# Proiect_TSC.net
KiCad netlist of a schematic drawn in EAGLE
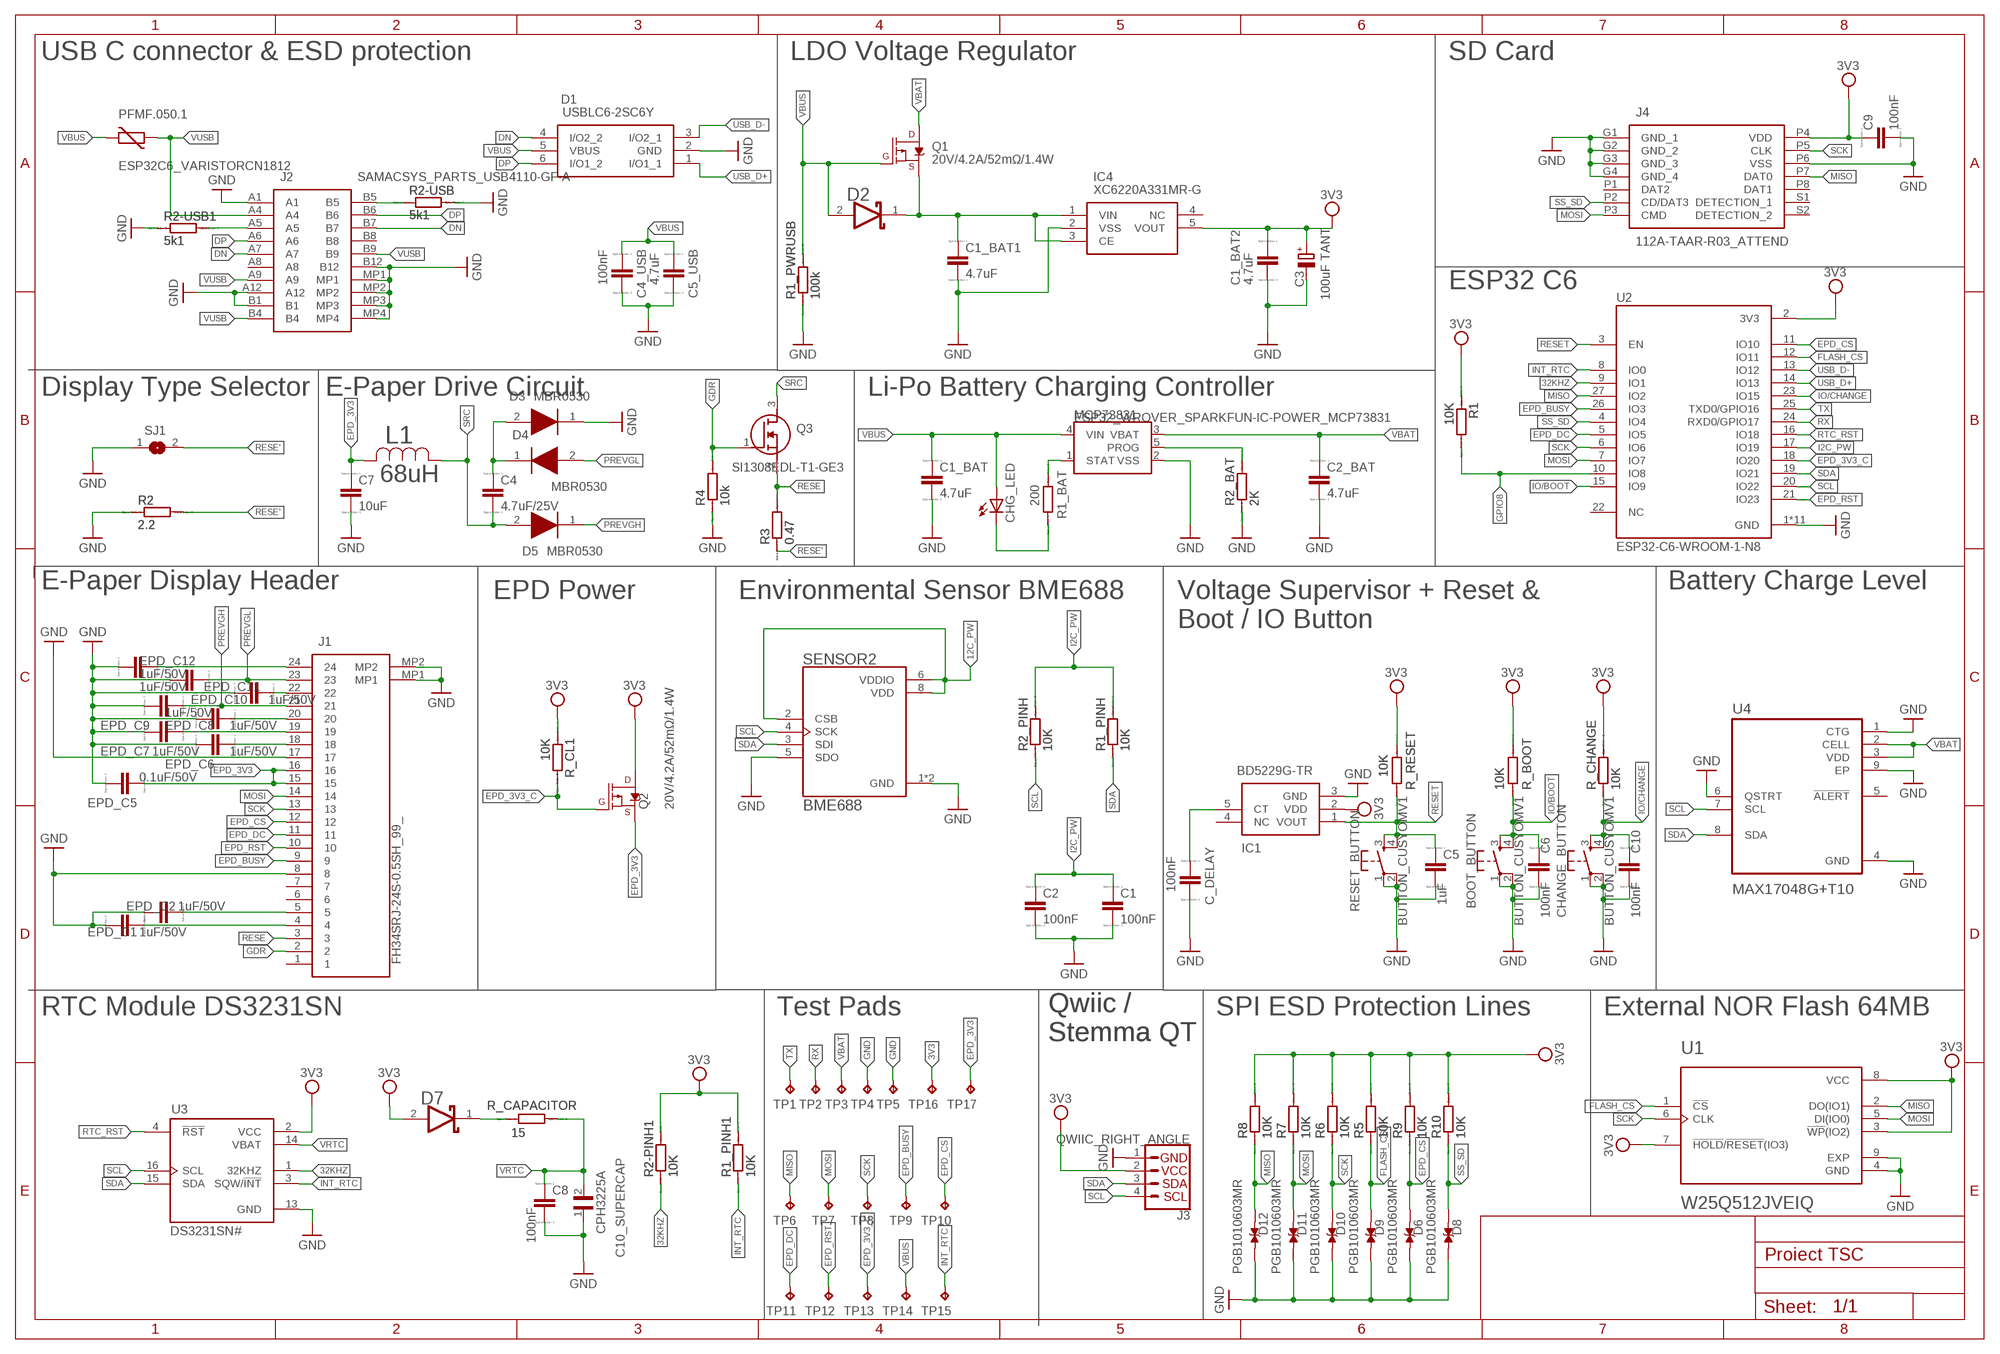
[diagram p0: schematic, sheet 1]

(export (version "E")
  (design (tool "Eeschema 10.0.6"))
  (components
    (comp (ref "BOOT_BUTTON")
      (value "BUTTON_CUSYOMV1")
      (footprint "eagle-import:MYBUTTON")
      (libsource (lib "eagle-import") (part "BUTTON_CUSYOMV1"))
    )
    (comp (ref "C1")
      (value "100nF")
      (footprint "eagle-import:EAGLE-LTSPICE_C0402")
      (libsource (lib "eagle-import") (part "EAGLE-LTSPICE_CC0402"))
    )
    (comp (ref "C1_BAT")
      (value "4.7uF")
      (footprint "eagle-import:EAGLE-LTSPICE_C0402")
      (libsource (lib "eagle-import") (part "EAGLE-LTSPICE_CC0402"))
    )
    (comp (ref "C1_BAT1")
      (value "4.7uF")
      (footprint "eagle-import:EAGLE-LTSPICE_C0402")
      (libsource (lib "eagle-import") (part "EAGLE-LTSPICE_CC0402"))
    )
    (comp (ref "C1_BAT2")
      (value "4.7uF")
      (footprint "eagle-import:EAGLE-LTSPICE_C0402")
      (libsource (lib "eagle-import") (part "EAGLE-LTSPICE_CC0402"))
    )
    (comp (ref "C2")
      (value "100nF")
      (footprint "eagle-import:EAGLE-LTSPICE_C0402")
      (libsource (lib "eagle-import") (part "EAGLE-LTSPICE_CC0402"))
    )
    (comp (ref "C2_BAT")
      (value "4.7uF")
      (footprint "eagle-import:EAGLE-LTSPICE_C0402")
      (libsource (lib "eagle-import") (part "EAGLE-LTSPICE_CC0402"))
    )
    (comp (ref "C3")
      (value "100uF TANT")
      (footprint "eagle-import:RCL_CT3528")
      (libsource (lib "eagle-import") (part "RCL_CPOL-EUCT3528"))
    )
    (comp (ref "C4")
      (value "4.7uF/25V")
      (footprint "eagle-import:EAGLE-LTSPICE_C0402")
      (libsource (lib "eagle-import") (part "EAGLE-LTSPICE_CC0402"))
    )
    (comp (ref "C4_USB")
      (value "100nF")
      (footprint "eagle-import:EAGLE-LTSPICE_C0402")
      (libsource (lib "eagle-import") (part "EAGLE-LTSPICE_CC0402"))
    )
    (comp (ref "C5")
      (value "1uF")
      (footprint "eagle-import:EAGLE-LTSPICE_C0402")
      (libsource (lib "eagle-import") (part "EAGLE-LTSPICE_CC0402"))
    )
    (comp (ref "C5_USB")
      (value "4.7uF")
      (footprint "eagle-import:EAGLE-LTSPICE_C0402")
      (libsource (lib "eagle-import") (part "EAGLE-LTSPICE_CC0402"))
    )
    (comp (ref "C6")
      (value "100nF")
      (footprint "eagle-import:EAGLE-LTSPICE_C0402")
      (libsource (lib "eagle-import") (part "EAGLE-LTSPICE_CC0402"))
    )
    (comp (ref "C7")
      (value "10uF")
      (footprint "eagle-import:EAGLE-LTSPICE_C0402")
      (libsource (lib "eagle-import") (part "EAGLE-LTSPICE_CC0402"))
    )
    (comp (ref "C8")
      (value "100nF")
      (footprint "eagle-import:EAGLE-LTSPICE_C0402")
      (libsource (lib "eagle-import") (part "EAGLE-LTSPICE_CC0402"))
    )
    (comp (ref "C9")
      (value "100nF")
      (footprint "eagle-import:EAGLE-LTSPICE_C0402")
      (libsource (lib "eagle-import") (part "EAGLE-LTSPICE_CC0402"))
    )
    (comp (ref "C10")
      (value "100nF")
      (footprint "eagle-import:EAGLE-LTSPICE_C0402")
      (libsource (lib "eagle-import") (part "EAGLE-LTSPICE_CC0402"))
    )
    (comp (ref "C10_SUPERCAP")
      (value "CPH3225A")
      (footprint "eagle-import:CAPCP3225X100N")
      (fields (field (name "MF") "Seiko Instruments"))
      (libsource (lib "eagle-import") (part "CPH3225A"))
    )
    (comp (ref "CHANGE_BUTTON")
      (value "BUTTON_CUSYOMV1")
      (footprint "eagle-import:MYBUTTON")
      (libsource (lib "eagle-import") (part "BUTTON_CUSYOMV1"))
    )
    (comp (ref "CHG_LED")
      (value "ADAFRUIT_LEDCHIP-LED0603")
      (footprint "eagle-import:ADAFRUIT_CHIP-LED0603")
      (libsource (lib "eagle-import") (part "ADAFRUIT_LEDCHIP-LED0603"))
    )
    (comp (ref "C_DELAY")
      (value "100nF")
      (footprint "eagle-import:EAGLE-LTSPICE_C0402")
      (libsource (lib "eagle-import") (part "EAGLE-LTSPICE_CC0402"))
    )
    (comp (ref "D1")
      (value "USBLC6-2SC6Y")
      (footprint "eagle-import:SOT95P280X145-6N")
      (fields (field (name "MF") "STMicroelectronics"))
      (libsource (lib "eagle-import") (part "USBLC6-2SC6Y"))
    )
    (comp (ref "D2")
      (value "SD0805S020S1R0")
      (footprint "eagle-import:ESP32_WROVER_AVX---SD0805S020S1R0_AVX_SD0805S020S1R0_0")
      (fields
        (field (name "DIGIKEY_PART_NUMBER") "478-7800-1-ND")
        (field (name "MF") "AVX")
        (field (name "MOUSER_PART_NUMBER") "581-SD0805S020S1R0")
      )
      (libsource (lib "eagle-import") (part "ESP32_WROVER_AVX---SD0805S020S1R0_AVX_SD0805S020S1R0_0_0AVX_SD0805S020S1R0_0_0"))
    )
    (comp (ref "D3")
      (value "MBR0530")
      (footprint "eagle-import:SOD3716X135N")
      (fields (field (name "MF") "ON Semiconductor"))
      (libsource (lib "eagle-import") (part "MBR0530"))
    )
    (comp (ref "D4")
      (value "MBR0530")
      (footprint "eagle-import:SOD3716X135N")
      (fields (field (name "MF") "ON Semiconductor"))
      (libsource (lib "eagle-import") (part "MBR0530"))
    )
    (comp (ref "D5")
      (value "MBR0530")
      (footprint "eagle-import:SOD3716X135N")
      (fields (field (name "MF") "ON Semiconductor"))
      (libsource (lib "eagle-import") (part "MBR0530"))
    )
    (comp (ref "D6")
      (value "PGB1010603MR")
      (footprint "eagle-import:DIOC1608X36N")
      (fields (field (name "MF") "Littelfuse Inc."))
      (libsource (lib "eagle-import") (part "PGB1010603MR"))
    )
    (comp (ref "D7")
      (value "ESP32_WROVER_AVX---SD0805S020S1R0_AVX_SD0805S020S1R0_0_0AVX_SD0805S020S1R0_0_0")
      (footprint "eagle-import:ESP32_WROVER_AVX---SD0805S020S1R0_AVX_SD0805S020S1R0_0")
      (fields
        (field (name "DIGIKEY_PART_NUMBER") "478-7800-1-ND")
        (field (name "MF") "AVX")
        (field (name "MOUSER_PART_NUMBER") "581-SD0805S020S1R0")
      )
      (libsource (lib "eagle-import") (part "ESP32_WROVER_AVX---SD0805S020S1R0_AVX_SD0805S020S1R0_0_0AVX_SD0805S020S1R0_0_0"))
    )
    (comp (ref "D8")
      (value "PGB1010603MR")
      (footprint "eagle-import:DIOC1608X36N")
      (fields (field (name "MF") "Littelfuse Inc."))
      (libsource (lib "eagle-import") (part "PGB1010603MR"))
    )
    (comp (ref "D9")
      (value "PGB1010603MR")
      (footprint "eagle-import:DIOC1608X36N")
      (fields (field (name "MF") "Littelfuse Inc."))
      (libsource (lib "eagle-import") (part "PGB1010603MR"))
    )
    (comp (ref "D10")
      (value "PGB1010603MR")
      (footprint "eagle-import:DIOC1608X36N")
      (fields (field (name "MF") "Littelfuse Inc."))
      (libsource (lib "eagle-import") (part "PGB1010603MR"))
    )
    (comp (ref "D11")
      (value "PGB1010603MR")
      (footprint "eagle-import:DIOC1608X36N")
      (fields (field (name "MF") "Littelfuse Inc."))
      (libsource (lib "eagle-import") (part "PGB1010603MR"))
    )
    (comp (ref "D12")
      (value "PGB1010603MR")
      (footprint "eagle-import:DIOC1608X36N")
      (fields (field (name "MF") "Littelfuse Inc."))
      (libsource (lib "eagle-import") (part "PGB1010603MR"))
    )
    (comp (ref "EPD_C1")
      (value "1uF/50V")
      (footprint "eagle-import:EAGLE-LTSPICE_C0402")
      (libsource (lib "eagle-import") (part "EAGLE-LTSPICE_CC0402"))
    )
    (comp (ref "EPD_C2")
      (value "1uF/50V")
      (footprint "eagle-import:EAGLE-LTSPICE_C0402")
      (libsource (lib "eagle-import") (part "EAGLE-LTSPICE_CC0402"))
    )
    (comp (ref "EPD_C5")
      (value "0.1uF/50V")
      (footprint "eagle-import:EAGLE-LTSPICE_C0402")
      (libsource (lib "eagle-import") (part "EAGLE-LTSPICE_CC0402"))
    )
    (comp (ref "EPD_C6")
      (value "1uF/50V")
      (footprint "eagle-import:EAGLE-LTSPICE_C0402")
      (libsource (lib "eagle-import") (part "EAGLE-LTSPICE_CC0402"))
    )
    (comp (ref "EPD_C7")
      (value "1uF/50V")
      (footprint "eagle-import:EAGLE-LTSPICE_C0402")
      (libsource (lib "eagle-import") (part "EAGLE-LTSPICE_CC0402"))
    )
    (comp (ref "EPD_C8")
      (value "1uF/50V")
      (footprint "eagle-import:EAGLE-LTSPICE_C0402")
      (libsource (lib "eagle-import") (part "EAGLE-LTSPICE_CC0402"))
    )
    (comp (ref "EPD_C9")
      (value "1uF/50V")
      (footprint "eagle-import:EAGLE-LTSPICE_C0402")
      (libsource (lib "eagle-import") (part "EAGLE-LTSPICE_CC0402"))
    )
    (comp (ref "EPD_C10")
      (value "1uF/50V")
      (footprint "eagle-import:EAGLE-LTSPICE_C0402")
      (libsource (lib "eagle-import") (part "EAGLE-LTSPICE_CC0402"))
    )
    (comp (ref "EPD_C11")
      (value "1uF/50V")
      (footprint "eagle-import:EAGLE-LTSPICE_C0402")
      (libsource (lib "eagle-import") (part "EAGLE-LTSPICE_CC0402"))
    )
    (comp (ref "EPD_C12")
      (value "1uF/50V")
      (footprint "eagle-import:EAGLE-LTSPICE_C0402")
      (libsource (lib "eagle-import") (part "EAGLE-LTSPICE_CC0402"))
    )
    (comp (ref "IC1")
      (value "BD5229G-TR")
      (footprint "eagle-import:SOT95P280X120-5N")
      (fields (field (name "MOUSER_PART_NUMBER") "755-BD5229G-TR"))
      (libsource (lib "eagle-import") (part "BD5229G-TR"))
    )
    (comp (ref "IC4")
      (value "XC6220A331MR-G")
      (footprint "eagle-import:SOT95P280X120-5N")
      (fields (field (name "MOUSER_PART_NUMBER") "865-XC6220A331MR-G"))
      (libsource (lib "eagle-import") (part "XC6220A331MR-G"))
    )
    (comp (ref "J1")
      (value "FH34SRJ-24S-0.5SH_99_")
      (footprint "eagle-import:FH34SRJ24S05SH99")
      (fields
        (field (name "MANUFACTURER_PART_NUMBER") "FH34SRJ-24S-0.5SH(99)")
        (field (name "MOUSER_PART_NUMBER") "798-FH34SRJ24S05SH99")
      )
      (libsource (lib "eagle-import") (part "FH34SRJ-24S-0.5SH_99_"))
    )
    (comp (ref "J2")
      (value "SAMACSYS_PARTS_USB4110-GF-A")
      (footprint "eagle-import:SAMACSYS_PARTS_USB4110GFA")
      (fields
        (field (name "MANUFACTURER_PART_NUMBER") "USB4110-GF-A")
        (field (name "MOUSER_PART_NUMBER") "640-USB4110-GF-A")
      )
      (libsource (lib "eagle-import") (part "SAMACSYS_PARTS_USB4110-GF-A"))
    )
    (comp (ref "J3")
      (value "QWIIC_RIGHT_ANGLE")
      (footprint "eagle-import:JST04_1MM_RA")
      (libsource (lib "eagle-import") (part "QWIIC_CONNECTORJS-1MM"))
    )
    (comp (ref "J4")
      (value "112A-TAAR-R03_ATTEND")
      (footprint "eagle-import:112ATAARR03ATTEND")
      (fields (field (name "MANUFACTURER_PART_NUMBER") "112A-TAAR-R03 ATTEND"))
      (libsource (lib "eagle-import") (part "112A-TAAR-R03_ATTEND"))
    )
    (comp (ref "L1")
      (value "68uH")
      (footprint "eagle-import:IND_4828-WE-TPC_WRE")
      (fields
        (field (name "MANUFACTURER_PART_NUMBER") "744043680")
        (field (name "COPYRIGHT") "Copyright (C) 2024 Ultra Librarian. All rights reserved.")
      )
      (libsource (lib "eagle-import") (part "744043680IND_4828-WE-TPC_WRE"))
    )
    (comp (ref "MCP73831")
      (value "ESP32_WROVER_SPARKFUN-IC-POWER_MCP73831")
      (footprint "eagle-import:ESP32_WROVER_SPARKFUN-IC-POWER_SOT23-5")
      (libsource (lib "eagle-import") (part "ESP32_WROVER_SPARKFUN-IC-POWER_MCP73831"))
    )
    (comp (ref "PFMF.050.1")
      (value "ESP32C6_VARISTORCN1812")
      (footprint "eagle-import:ESP32C6_VARISTOR_CT_CN1812")
      (libsource (lib "eagle-import") (part "ESP32C6_VARISTORCN1812"))
    )
    (comp (ref "Q1")
      (value "20V/4.2A/52mΩ/1.4W")
      (footprint "eagle-import:ESP32_WROVER_SPARKFUN-DISCRETESEMI_SOT23-3")
      (libsource (lib "eagle-import") (part "ESP32_WROVER_SPARKFUN-DISCRETESEMI_MOSFET_PCH-DMG2305UX-7"))
    )
    (comp (ref "Q2")
      (value "20V/4.2A/52mΩ/1.4W")
      (footprint "eagle-import:ESP32_WROVER_SPARKFUN-DISCRETESEMI_SOT23-3")
      (libsource (lib "eagle-import") (part "ESP32_WROVER_SPARKFUN-DISCRETESEMI_MOSFET_PCH-DMG2305UX-7"))
    )
    (comp (ref "Q3")
      (value "SI1308EDL-T1-GE3")
      (footprint "eagle-import:SOT65P210X110-3N")
      (fields (field (name "MF") "Vishay Siliconix"))
      (libsource (lib "eagle-import") (part "SI1308EDL-T1-GE3"))
    )
    (comp (ref "R1")
      (value "10K")
      (footprint "eagle-import:ESP32_WROVER_EAGLE-LTSPICE_R0402")
      (libsource (lib "eagle-import") (part "ESP32_WROVER_EAGLE-LTSPICE_RR0402"))
    )
    (comp (ref "R1_BAT")
      (value "200")
      (footprint "eagle-import:ESP32_WROVER_EAGLE-LTSPICE_R0402")
      (libsource (lib "eagle-import") (part "ESP32_WROVER_EAGLE-LTSPICE_RR0402"))
    )
    (comp (ref "R1_PINH")
      (value "10K")
      (footprint "eagle-import:ESP32_WROVER_EAGLE-LTSPICE_R0402")
      (libsource (lib "eagle-import") (part "ESP32_WROVER_EAGLE-LTSPICE_RR0402"))
    )
    (comp (ref "R1_PINH1")
      (value "10K")
      (footprint "eagle-import:ESP32_WROVER_EAGLE-LTSPICE_R0402")
      (libsource (lib "eagle-import") (part "ESP32_WROVER_EAGLE-LTSPICE_RR0402"))
    )
    (comp (ref "R1_PWRUSB")
      (value "100k")
      (footprint "eagle-import:ESP32_WROVER_EAGLE-LTSPICE_R0402")
      (libsource (lib "eagle-import") (part "ESP32_WROVER_EAGLE-LTSPICE_RR0402"))
    )
    (comp (ref "R2")
      (value "2.2")
      (footprint "eagle-import:ESP32_WROVER_EAGLE-LTSPICE_R0402")
      (libsource (lib "eagle-import") (part "ESP32_WROVER_EAGLE-LTSPICE_RR0402"))
    )
    (comp (ref "R2-PINH1")
      (value "10K")
      (footprint "eagle-import:ESP32_WROVER_EAGLE-LTSPICE_R0402")
      (libsource (lib "eagle-import") (part "ESP32_WROVER_EAGLE-LTSPICE_RR0402"))
    )
    (comp (ref "R2-USB")
      (value "5k1")
      (footprint "eagle-import:ESP32_WROVER_EAGLE-LTSPICE_R0402")
      (libsource (lib "eagle-import") (part "ESP32_WROVER_EAGLE-LTSPICE_RR0402"))
    )
    (comp (ref "R2-USB1")
      (value "5k1")
      (footprint "eagle-import:ESP32_WROVER_EAGLE-LTSPICE_R0402")
      (libsource (lib "eagle-import") (part "ESP32_WROVER_EAGLE-LTSPICE_RR0402"))
    )
    (comp (ref "R2_BAT")
      (value "2K")
      (footprint "eagle-import:ESP32_WROVER_EAGLE-LTSPICE_R0402")
      (libsource (lib "eagle-import") (part "ESP32_WROVER_EAGLE-LTSPICE_RR0402"))
    )
    (comp (ref "R2_PINH")
      (value "10K")
      (footprint "eagle-import:ESP32_WROVER_EAGLE-LTSPICE_R0402")
      (libsource (lib "eagle-import") (part "ESP32_WROVER_EAGLE-LTSPICE_RR0402"))
    )
    (comp (ref "R3")
      (value "0.47")
      (footprint "eagle-import:ESP32_WROVER_EAGLE-LTSPICE_R0402")
      (libsource (lib "eagle-import") (part "ESP32_WROVER_EAGLE-LTSPICE_RR0402"))
    )
    (comp (ref "R4")
      (value "10k")
      (footprint "eagle-import:ESP32_WROVER_EAGLE-LTSPICE_R0402")
      (libsource (lib "eagle-import") (part "ESP32_WROVER_EAGLE-LTSPICE_RR0402"))
    )
    (comp (ref "R5")
      (value "10K")
      (footprint "eagle-import:ESP32_WROVER_EAGLE-LTSPICE_R0402")
      (libsource (lib "eagle-import") (part "ESP32_WROVER_EAGLE-LTSPICE_RR0402"))
    )
    (comp (ref "R6")
      (value "10K")
      (footprint "eagle-import:ESP32_WROVER_EAGLE-LTSPICE_R0402")
      (libsource (lib "eagle-import") (part "ESP32_WROVER_EAGLE-LTSPICE_RR0402"))
    )
    (comp (ref "R7")
      (value "10K")
      (footprint "eagle-import:ESP32_WROVER_EAGLE-LTSPICE_R0402")
      (libsource (lib "eagle-import") (part "ESP32_WROVER_EAGLE-LTSPICE_RR0402"))
    )
    (comp (ref "R8")
      (value "10K")
      (footprint "eagle-import:ESP32_WROVER_EAGLE-LTSPICE_R0402")
      (libsource (lib "eagle-import") (part "ESP32_WROVER_EAGLE-LTSPICE_RR0402"))
    )
    (comp (ref "R9")
      (value "10K")
      (footprint "eagle-import:ESP32_WROVER_EAGLE-LTSPICE_R0402")
      (libsource (lib "eagle-import") (part "ESP32_WROVER_EAGLE-LTSPICE_RR0402"))
    )
    (comp (ref "R10")
      (value "10K")
      (footprint "eagle-import:ESP32_WROVER_EAGLE-LTSPICE_R0402")
      (libsource (lib "eagle-import") (part "ESP32_WROVER_EAGLE-LTSPICE_RR0402"))
    )
    (comp (ref "RESET_BUTTON")
      (value "BUTTON_CUSYOMV1")
      (footprint "eagle-import:MYBUTTON")
      (libsource (lib "eagle-import") (part "BUTTON_CUSYOMV1"))
    )
    (comp (ref "R_BOOT")
      (value "10K")
      (footprint "eagle-import:ESP32_WROVER_EAGLE-LTSPICE_R0402")
      (libsource (lib "eagle-import") (part "ESP32_WROVER_EAGLE-LTSPICE_RR0402"))
    )
    (comp (ref "R_CAPACITOR")
      (value "15")
      (footprint "eagle-import:ESP32_WROVER_EAGLE-LTSPICE_R0402")
      (libsource (lib "eagle-import") (part "ESP32_WROVER_EAGLE-LTSPICE_RR0402"))
    )
    (comp (ref "R_CHANGE")
      (value "10K")
      (footprint "eagle-import:ESP32_WROVER_EAGLE-LTSPICE_R0402")
      (libsource (lib "eagle-import") (part "ESP32_WROVER_EAGLE-LTSPICE_RR0402"))
    )
    (comp (ref "R_CL1")
      (value "10K")
      (footprint "eagle-import:ESP32_WROVER_EAGLE-LTSPICE_R0402")
      (libsource (lib "eagle-import") (part "ESP32_WROVER_EAGLE-LTSPICE_RR0402"))
    )
    (comp (ref "R_RESET")
      (value "10K")
      (footprint "eagle-import:ESP32_WROVER_EAGLE-LTSPICE_R0402")
      (libsource (lib "eagle-import") (part "ESP32_WROVER_EAGLE-LTSPICE_RR0402"))
    )
    (comp (ref "SENSOR2")
      (value "BME688")
      (footprint "eagle-import:ESP32_WROVER_BME680_PSON80P300X300X100-8N")
      (fields (field (name "MF") "Bosch Sensortec") (field (name "MP") "BME680"))
      (libsource (lib "eagle-import") (part "ESP32_WROVER_BME680_BME680"))
    )
    (comp (ref "SJ1") (value "SJ") (footprint "eagle-import:SJ") (libsource (lib "eagle-import") (part "SJ")))
    (comp (ref "TP1")
      (value "TPTP20R")
      (footprint "eagle-import:TP20R")
      (libsource (lib "eagle-import") (part "TPTP20R"))
    )
    (comp (ref "TP2")
      (value "TPTP20R")
      (footprint "eagle-import:TP20R")
      (libsource (lib "eagle-import") (part "TPTP20R"))
    )
    (comp (ref "TP3")
      (value "TPTP20R")
      (footprint "eagle-import:TP20R")
      (libsource (lib "eagle-import") (part "TPTP20R"))
    )
    (comp (ref "TP4")
      (value "TPTP20R")
      (footprint "eagle-import:TP20R")
      (libsource (lib "eagle-import") (part "TPTP20R"))
    )
    (comp (ref "TP5")
      (value "TPTP20R")
      (footprint "eagle-import:TP20R")
      (libsource (lib "eagle-import") (part "TPTP20R"))
    )
    (comp (ref "TP6")
      (value "TPTP20R")
      (footprint "eagle-import:TP20R")
      (libsource (lib "eagle-import") (part "TPTP20R"))
    )
    (comp (ref "TP7")
      (value "TPTP20R")
      (footprint "eagle-import:TP20R")
      (libsource (lib "eagle-import") (part "TPTP20R"))
    )
    (comp (ref "TP8")
      (value "TPTP20R")
      (footprint "eagle-import:TP20R")
      (libsource (lib "eagle-import") (part "TPTP20R"))
    )
    (comp (ref "TP9")
      (value "TPTP20R")
      (footprint "eagle-import:TP20R")
      (libsource (lib "eagle-import") (part "TPTP20R"))
    )
    (comp (ref "TP10")
      (value "TPTP20R")
      (footprint "eagle-import:TP20R")
      (libsource (lib "eagle-import") (part "TPTP20R"))
    )
    (comp (ref "TP11")
      (value "TPTP20R")
      (footprint "eagle-import:TP20R")
      (libsource (lib "eagle-import") (part "TPTP20R"))
    )
    (comp (ref "TP12")
      (value "TPTP20R")
      (footprint "eagle-import:TP20R")
      (libsource (lib "eagle-import") (part "TPTP20R"))
    )
    (comp (ref "TP13")
      (value "TPTP20R")
      (footprint "eagle-import:TP20R")
      (libsource (lib "eagle-import") (part "TPTP20R"))
    )
    (comp (ref "TP14")
      (value "TPTP20R")
      (footprint "eagle-import:TP20R")
      (libsource (lib "eagle-import") (part "TPTP20R"))
    )
    (comp (ref "TP15")
      (value "TPTP20R")
      (footprint "eagle-import:TP20R")
      (libsource (lib "eagle-import") (part "TPTP20R"))
    )
    (comp (ref "TP16")
      (value "TPTP20R")
      (footprint "eagle-import:TP20R")
      (libsource (lib "eagle-import") (part "TPTP20R"))
    )
    (comp (ref "TP17")
      (value "TPTP20R")
      (footprint "eagle-import:TP20R")
      (libsource (lib "eagle-import") (part "TPTP20R"))
    )
    (comp (ref "U1")
      (value "W25Q512JVEIQ")
      (footprint "eagle-import:SON127P600X800X80-9N")
      (fields (field (name "MF") "Winbond Electronics"))
      (libsource (lib "eagle-import") (part "W25Q512JVEIQ"))
    )
    (comp (ref "U2")
      (value "ESP32-C6-WROOM-1-N8")
      (footprint "eagle-import:XCVR_ESP32-C6-WROOM-1-N8")
      (fields (field (name "MF") "Espressif Systems"))
      (libsource (lib "eagle-import") (part "ESP32-C6-WROOM-1-N8"))
    )
    (comp (ref "U3")
      (value "DS3231SN#")
      (footprint "eagle-import:SOIC127P1032X265-16N")
      (fields (field (name "MF") "Analog Devices"))
      (libsource (lib "eagle-import") (part "DS3231SN#"))
    )
    (comp (ref "U4")
      (value "MAX17048G+T10")
      (footprint "eagle-import:SON50P200X200X80-9N")
      (fields (field (name "MF") "Analog Devices"))
      (libsource (lib "eagle-import") (part "MAX17048G+T10"))
    )
  )
  (nets
    (net (code "1") (name "3V3") (class "Default")
      (node (ref "C1_BAT2") (pin "1") (pinfunction "1_1") (pintype "passive"))
      (node (ref "C3") (pin "+") (pinfunction "+_+") (pintype "passive"))
      (node (ref "C9") (pin "1") (pinfunction "1_1") (pintype "passive"))
      (node (ref "D7") (pin "2") (pinfunction "ANODE_2") (pintype "bidirectional"))
      (node (ref "IC1") (pin "2") (pinfunction "VDD_2") (pintype "bidirectional"))
      (node (ref "IC4") (pin "5") (pinfunction "VOUT_5") (pintype "bidirectional"))
      (node (ref "J3") (pin "2") (pinfunction "2_2") (pintype "power_in"))
      (node (ref "J4") (pin "P4") (pinfunction "VDD_P4") (pintype "bidirectional"))
      (node (ref "Q2") (pin "3") (pinfunction "D_3") (pintype "bidirectional"))
      (node (ref "R1") (pin "1") (pinfunction "1_1") (pintype "passive"))
      (node (ref "R10") (pin "2") (pinfunction "2_2") (pintype "passive"))
      (node (ref "R1_PINH1") (pin "2") (pinfunction "2_2") (pintype "passive"))
      (node (ref "R2-PINH1") (pin "2") (pinfunction "2_2") (pintype "passive"))
      (node (ref "R5") (pin "2") (pinfunction "2_2") (pintype "passive"))
      (node (ref "R6") (pin "2") (pinfunction "2_2") (pintype "passive"))
      (node (ref "R7") (pin "2") (pinfunction "2_2") (pintype "passive"))
      (node (ref "R8") (pin "2") (pinfunction "2_2") (pintype "passive"))
      (node (ref "R9") (pin "2") (pinfunction "2_2") (pintype "passive"))
      (node (ref "R_BOOT") (pin "2") (pinfunction "2_2") (pintype "passive"))
      (node (ref "R_CHANGE") (pin "2") (pinfunction "2_2") (pintype "passive"))
      (node (ref "R_CL1") (pin "1") (pinfunction "1_1") (pintype "passive"))
      (node (ref "R_RESET") (pin "2") (pinfunction "2_2") (pintype "passive"))
      (node (ref "TP16") (pin "TP") (pinfunction "TP_TP") (pintype "input"))
      (node (ref "U1") (pin "3") (pinfunction "~{WP}(IO2)_3") (pintype "bidirectional"))
      (node (ref "U1") (pin "7") (pinfunction "~{HOLD}/~{RESET}(IO3)_7") (pintype "bidirectional"))
      (node (ref "U1") (pin "8") (pinfunction "VCC_8") (pintype "power_in"))
      (node (ref "U2") (pin "2") (pinfunction "3V3_2") (pintype "power_in"))
      (node (ref "U3") (pin "2") (pinfunction "VCC_2") (pintype "power_in"))
    )
    (net (code "2") (name "12C_PW") (class "Default")
      (node (ref "SENSOR2") (pin "2") (pinfunction "CSB_2") (pintype "input"))
      (node (ref "SENSOR2") (pin "6") (pinfunction "VDDIO_6") (pintype "power_in"))
      (node (ref "SENSOR2") (pin "8") (pinfunction "VDD_8") (pintype "power_in"))
    )
    (net (code "3") (name "32KHZ") (class "Default")
      (node (ref "R2-PINH1") (pin "1") (pinfunction "1_1") (pintype "passive"))
      (node (ref "U2") (pin "9") (pinfunction "IO1_9") (pintype "bidirectional"))
      (node (ref "U3") (pin "1") (pinfunction "32KHZ_1") (pintype "output"))
    )
    (net (code "4") (name "DN") (class "Default")
      (node (ref "D1") (pin "4") (pinfunction "I/O2_2_4") (pintype "bidirectional"))
      (node (ref "J2") (pin "A7") (pinfunction "A7_A7") (pintype "bidirectional"))
      (node (ref "J2") (pin "B7") (pinfunction "B7_B7") (pintype "bidirectional"))
    )
    (net (code "5") (name "DP") (class "Default")
      (node (ref "D1") (pin "6") (pinfunction "I/O1_2_6") (pintype "bidirectional"))
      (node (ref "J2") (pin "A6") (pinfunction "A6_A6") (pintype "bidirectional"))
      (node (ref "J2") (pin "B6") (pinfunction "B6_B6") (pintype "bidirectional"))
    )
    (net (code "6") (name "EPD_3V3") (class "Default")
      (node (ref "C7") (pin "1") (pinfunction "1_1") (pintype "passive"))
      (node (ref "EPD_C5") (pin "1") (pinfunction "1_1") (pintype "passive"))
      (node (ref "J1") (pin "15") (pinfunction "15_15") (pintype "bidirectional"))
      (node (ref "J1") (pin "16") (pinfunction "16_16") (pintype "bidirectional"))
      (node (ref "L1") (pin "2") (pinfunction "2_2") (pintype "passive"))
      (node (ref "Q2") (pin "2") (pinfunction "S_2") (pintype "bidirectional"))
      (node (ref "TP17") (pin "TP") (pinfunction "TP_TP") (pintype "input"))
    )
    (net (code "7") (name "EPD_3V3_C") (class "Default")
      (node (ref "Q2") (pin "1") (pinfunction "G_1") (pintype "bidirectional"))
      (node (ref "R_CL1") (pin "2") (pinfunction "2_2") (pintype "passive"))
      (node (ref "TP13") (pin "TP") (pinfunction "TP_TP") (pintype "input"))
      (node (ref "U2") (pin "18") (pinfunction "IO20_18") (pintype "bidirectional"))
    )
    (net (code "8") (name "EPD_BUSY") (class "Default")
      (node (ref "J1") (pin "9") (pinfunction "9_9") (pintype "bidirectional"))
      (node (ref "TP9") (pin "TP") (pinfunction "TP_TP") (pintype "input"))
      (node (ref "U2") (pin "26") (pinfunction "IO3_26") (pintype "bidirectional"))
    )
    (net (code "9") (name "EPD_CS") (class "Default")
      (node (ref "D6") (pin "2") (pinfunction "2_2") (pintype "passive"))
      (node (ref "J1") (pin "12") (pinfunction "12_12") (pintype "bidirectional"))
      (node (ref "R9") (pin "1") (pinfunction "1_1") (pintype "passive"))
      (node (ref "TP10") (pin "TP") (pinfunction "TP_TP") (pintype "input"))
      (node (ref "U2") (pin "11") (pinfunction "IO10_11") (pintype "bidirectional"))
    )
    (net (code "10") (name "EPD_DC") (class "Default")
      (node (ref "J1") (pin "11") (pinfunction "11_11") (pintype "bidirectional"))
      (node (ref "TP11") (pin "TP") (pinfunction "TP_TP") (pintype "input"))
      (node (ref "U2") (pin "5") (pinfunction "IO5_5") (pintype "bidirectional"))
    )
    (net (code "11") (name "EPD_RST") (class "Default")
      (node (ref "J1") (pin "10") (pinfunction "10_10") (pintype "bidirectional"))
      (node (ref "TP12") (pin "TP") (pinfunction "TP_TP") (pintype "input"))
      (node (ref "U2") (pin "21") (pinfunction "IO23_21") (pintype "bidirectional"))
    )
    (net (code "12") (name "FLASH_CS") (class "Default")
      (node (ref "D9") (pin "2") (pinfunction "2_2") (pintype "passive"))
      (node (ref "R5") (pin "1") (pinfunction "1_1") (pintype "passive"))
      (node (ref "U1") (pin "1") (pinfunction "~{CS}_1") (pintype "input"))
      (node (ref "U2") (pin "12") (pinfunction "IO11_12") (pintype "bidirectional"))
    )
    (net (code "13") (name "GDR") (class "Default")
      (node (ref "J1") (pin "2") (pinfunction "2_2") (pintype "bidirectional"))
      (node (ref "Q3") (pin "1") (pinfunction "G_1") (pintype "bidirectional"))
      (node (ref "R4") (pin "2") (pinfunction "2_2") (pintype "passive"))
    )
    (net (code "14") (name "GND") (class "Default")
      (node (ref "BOOT_BUTTON") (pin "1") (pinfunction "1_1") (pintype "passive"))
      (node (ref "BOOT_BUTTON") (pin "2") (pinfunction "2_2") (pintype "passive"))
      (node (ref "C1") (pin "2") (pinfunction "2_2") (pintype "passive"))
      (node (ref "C10") (pin "2") (pinfunction "2_2") (pintype "passive"))
      (node (ref "C10_SUPERCAP") (pin "1") (pinfunction "1_1") (pintype "passive"))
      (node (ref "C1_BAT") (pin "2") (pinfunction "2_2") (pintype "passive"))
      (node (ref "C1_BAT1") (pin "2") (pinfunction "2_2") (pintype "passive"))
      (node (ref "C1_BAT2") (pin "2") (pinfunction "2_2") (pintype "passive"))
      (node (ref "C2") (pin "2") (pinfunction "2_2") (pintype "passive"))
      (node (ref "C2_BAT") (pin "2") (pinfunction "2_2") (pintype "passive"))
      (node (ref "C3") (pin "-") (pinfunction "-_-") (pintype "passive"))
      (node (ref "C4_USB") (pin "2") (pinfunction "2_2") (pintype "passive"))
      (node (ref "C5") (pin "2") (pinfunction "2_2") (pintype "passive"))
      (node (ref "C5_USB") (pin "2") (pinfunction "2_2") (pintype "passive"))
      (node (ref "C6") (pin "2") (pinfunction "2_2") (pintype "passive"))
      (node (ref "C7") (pin "2") (pinfunction "2_2") (pintype "passive"))
      (node (ref "C8") (pin "2") (pinfunction "2_2") (pintype "passive"))
      (node (ref "C9") (pin "2") (pinfunction "2_2") (pintype "passive"))
      (node (ref "CHANGE_BUTTON") (pin "1") (pinfunction "1_1") (pintype "passive"))
      (node (ref "CHANGE_BUTTON") (pin "2") (pinfunction "2_2") (pintype "passive"))
      (node (ref "C_DELAY") (pin "2") (pinfunction "2_2") (pintype "passive"))
      (node (ref "D1") (pin "2") (pinfunction "GND_2") (pintype "bidirectional"))
      (node (ref "D10") (pin "1") (pinfunction "1_1") (pintype "passive"))
      (node (ref "D11") (pin "1") (pinfunction "1_1") (pintype "passive"))
      (node (ref "D12") (pin "1") (pinfunction "1_1") (pintype "passive"))
      (node (ref "D3") (pin "1") (pinfunction "K_1") (pintype "bidirectional"))
      (node (ref "D6") (pin "1") (pinfunction "1_1") (pintype "passive"))
      (node (ref "D8") (pin "1") (pinfunction "1_1") (pintype "passive"))
      (node (ref "D9") (pin "1") (pinfunction "1_1") (pintype "passive"))
      (node (ref "EPD_C1") (pin "2") (pinfunction "2_2") (pintype "passive"))
      (node (ref "EPD_C10") (pin "2") (pinfunction "2_2") (pintype "passive"))
      (node (ref "EPD_C11") (pin "2") (pinfunction "2_2") (pintype "passive"))
      (node (ref "EPD_C12") (pin "2") (pinfunction "2_2") (pintype "passive"))
      (node (ref "EPD_C2") (pin "2") (pinfunction "2_2") (pintype "passive"))
      (node (ref "EPD_C5") (pin "2") (pinfunction "2_2") (pintype "passive"))
      (node (ref "EPD_C6") (pin "2") (pinfunction "2_2") (pintype "passive"))
      (node (ref "EPD_C7") (pin "2") (pinfunction "2_2") (pintype "passive"))
      (node (ref "EPD_C8") (pin "2") (pinfunction "2_2") (pintype "passive"))
      (node (ref "EPD_C9") (pin "2") (pinfunction "2_2") (pintype "passive"))
      (node (ref "IC1") (pin "3") (pinfunction "GND_3") (pintype "bidirectional"))
      (node (ref "IC4") (pin "2") (pinfunction "VSS_2") (pintype "bidirectional"))
      (node (ref "J1") (pin "17") (pinfunction "17_17") (pintype "bidirectional"))
      (node (ref "J1") (pin "8") (pinfunction "8_8") (pintype "bidirectional"))
      (node (ref "J1") (pin "MP1") (pinfunction "MP1_MP1") (pintype "bidirectional"))
      (node (ref "J1") (pin "MP2") (pinfunction "MP2_MP2") (pintype "bidirectional"))
      (node (ref "J2") (pin "A1") (pinfunction "A1_A1") (pintype "bidirectional"))
      (node (ref "J2") (pin "A12") (pinfunction "A12_A12") (pintype "bidirectional"))
      (node (ref "J2") (pin "B1") (pinfunction "B1_B1") (pintype "bidirectional"))
      (node (ref "J2") (pin "B12") (pinfunction "B12_B12") (pintype "bidirectional"))
      (node (ref "J2") (pin "MP1") (pinfunction "MP1_MP1") (pintype "bidirectional"))
      (node (ref "J2") (pin "MP2") (pinfunction "MP2_MP2") (pintype "bidirectional"))
      (node (ref "J2") (pin "MP3") (pinfunction "MP3_MP3") (pintype "bidirectional"))
      (node (ref "J2") (pin "MP4") (pinfunction "MP4_MP4") (pintype "bidirectional"))
      (node (ref "J3") (pin "1") (pinfunction "1_1") (pintype "power_in"))
      (node (ref "J4") (pin "G1") (pinfunction "GND_1_G1") (pintype "bidirectional"))
      (node (ref "J4") (pin "G2") (pinfunction "GND_2_G2") (pintype "bidirectional"))
      (node (ref "J4") (pin "G3") (pinfunction "GND_3_G3") (pintype "bidirectional"))
      (node (ref "J4") (pin "G4") (pinfunction "GND_4_G4") (pintype "bidirectional"))
      (node (ref "J4") (pin "P6") (pinfunction "VSS_P6") (pintype "bidirectional"))
      (node (ref "MCP73831") (pin "2") (pinfunction "VSS_2") (pintype "power_in"))
      (node (ref "R1_PWRUSB") (pin "1") (pinfunction "1_1") (pintype "passive"))
      (node (ref "R2") (pin "1") (pinfunction "1_1") (pintype "passive"))
      (node (ref "R2-USB") (pin "2") (pinfunction "2_2") (pintype "passive"))
      (node (ref "R2-USB1") (pin "1") (pinfunction "1_1") (pintype "passive"))
      (node (ref "R2_BAT") (pin "1") (pinfunction "1_1") (pintype "passive"))
      (node (ref "R4") (pin "1") (pinfunction "1_1") (pintype "passive"))
      (node (ref "RESET_BUTTON") (pin "1") (pinfunction "1_1") (pintype "passive"))
      (node (ref "RESET_BUTTON") (pin "2") (pinfunction "2_2") (pintype "passive"))
      (node (ref "SENSOR2") (pin "1") (pinfunction "GND_1") (pintype "power_in"))
      (node (ref "SENSOR2") (pin "5") (pinfunction "SDO_5") (pintype "bidirectional"))
      (node (ref "SENSOR2") (pin "7") (pinfunction "GND_7") (pintype "power_in"))
      (node (ref "SJ1") (pin "1") (pinfunction "1_1") (pintype "passive"))
      (node (ref "TP4") (pin "TP") (pinfunction "TP_TP") (pintype "input"))
      (node (ref "TP5") (pin "TP") (pinfunction "TP_TP") (pintype "input"))
      (node (ref "U1") (pin "4") (pinfunction "GND_4") (pintype "power_in"))
      (node (ref "U1") (pin "9") (pinfunction "EXP_9") (pintype "passive"))
      (node (ref "U2") (pin "1") (pinfunction "GND_1") (pintype "power_in"))
      (node (ref "U2") (pin "28") (pinfunction "GND_28") (pintype "power_in"))
      (node (ref "U2") (pin "29_1") (pinfunction "GND_29_1") (pintype "power_in"))
      (node (ref "U2") (pin "29_2") (pinfunction "GND_29_2") (pintype "power_in"))
      (node (ref "U2") (pin "29_3") (pinfunction "GND_29_3") (pintype "power_in"))
      (node (ref "U2") (pin "29_4") (pinfunction "GND_29_4") (pintype "power_in"))
      (node (ref "U2") (pin "29_5") (pinfunction "GND_29_5") (pintype "power_in"))
      (node (ref "U2") (pin "29_6") (pinfunction "GND_29_6") (pintype "power_in"))
      (node (ref "U2") (pin "29_7") (pinfunction "GND_29_7") (pintype "power_in"))
      (node (ref "U2") (pin "29_8") (pinfunction "GND_29_8") (pintype "power_in"))
      (node (ref "U2") (pin "29_9") (pinfunction "GND_29_9") (pintype "power_in"))
      (node (ref "U3") (pin "13") (pinfunction "GND_13") (pintype "power_in"))
      (node (ref "U4") (pin "1") (pinfunction "CTG_1") (pintype "power_in"))
      (node (ref "U4") (pin "4") (pinfunction "GND_4") (pintype "power_in"))
      (node (ref "U4") (pin "6") (pinfunction "QSTRT_6") (pintype "input"))
      (node (ref "U4") (pin "9") (pinfunction "EP_9") (pintype "power_in"))
    )
    (net (code "15") (name "GPIO8") (class "Default")
      (node (ref "R1") (pin "2") (pinfunction "2_2") (pintype "passive"))
      (node (ref "U2") (pin "10") (pinfunction "IO8_10") (pintype "bidirectional"))
    )
    (net (code "16") (name "I2C_PW") (class "Default")
      (node (ref "C1") (pin "1") (pinfunction "1_1") (pintype "passive"))
      (node (ref "C2") (pin "1") (pinfunction "1_1") (pintype "passive"))
      (node (ref "R1_PINH") (pin "2") (pinfunction "2_2") (pintype "passive"))
      (node (ref "R2_PINH") (pin "2") (pinfunction "2_2") (pintype "passive"))
      (node (ref "U2") (pin "17") (pinfunction "IO19_17") (pintype "bidirectional"))
    )
    (net (code "17") (name "INT_RTC") (class "Default")
      (node (ref "R1_PINH1") (pin "1") (pinfunction "1_1") (pintype "passive"))
      (node (ref "TP15") (pin "TP") (pinfunction "TP_TP") (pintype "input"))
      (node (ref "U2") (pin "8") (pinfunction "IO0_8") (pintype "bidirectional"))
      (node (ref "U3") (pin "3") (pinfunction "SQW/~{INT}_3") (pintype "output"))
    )
    (net (code "18") (name "IO{slash}BOOT") (class "Default")
      (node (ref "BOOT_BUTTON") (pin "3") (pinfunction "3_3") (pintype "passive"))
      (node (ref "BOOT_BUTTON") (pin "4") (pinfunction "4_4") (pintype "passive"))
      (node (ref "C6") (pin "1") (pinfunction "1_1") (pintype "passive"))
      (node (ref "R_BOOT") (pin "1") (pinfunction "1_1") (pintype "passive"))
      (node (ref "U2") (pin "15") (pinfunction "IO9_15") (pintype "bidirectional"))
    )
    (net (code "19") (name "IO{slash}CHANGE") (class "Default")
      (node (ref "C10") (pin "1") (pinfunction "1_1") (pintype "passive"))
      (node (ref "CHANGE_BUTTON") (pin "3") (pinfunction "3_3") (pintype "passive"))
      (node (ref "CHANGE_BUTTON") (pin "4") (pinfunction "4_4") (pintype "passive"))
      (node (ref "R_CHANGE") (pin "1") (pinfunction "1_1") (pintype "passive"))
      (node (ref "U2") (pin "23") (pinfunction "IO15_23") (pintype "bidirectional"))
    )
    (net (code "20") (name "MISO") (class "Default")
      (node (ref "D12") (pin "2") (pinfunction "2_2") (pintype "passive"))
      (node (ref "J4") (pin "P7") (pinfunction "DAT0_P7") (pintype "bidirectional"))
      (node (ref "R8") (pin "1") (pinfunction "1_1") (pintype "passive"))
      (node (ref "TP6") (pin "TP") (pinfunction "TP_TP") (pintype "input"))
      (node (ref "U1") (pin "2") (pinfunction "DO(IO1)_2") (pintype "bidirectional"))
      (node (ref "U2") (pin "27") (pinfunction "IO2_27") (pintype "bidirectional"))
    )
    (net (code "21") (name "MOSI") (class "Default")
      (node (ref "D11") (pin "2") (pinfunction "2_2") (pintype "passive"))
      (node (ref "J1") (pin "14") (pinfunction "14_14") (pintype "bidirectional"))
      (node (ref "J4") (pin "P3") (pinfunction "CMD_P3") (pintype "bidirectional"))
      (node (ref "R7") (pin "1") (pinfunction "1_1") (pintype "passive"))
      (node (ref "TP7") (pin "TP") (pinfunction "TP_TP") (pintype "input"))
      (node (ref "U1") (pin "5") (pinfunction "DI(IO0)_5") (pintype "bidirectional"))
      (node (ref "U2") (pin "7") (pinfunction "IO7_7") (pintype "bidirectional"))
    )
    (net (code "22") (name "Net-(CHG_LED-PadC)") (class "Default")
      (node (ref "CHG_LED") (pin "C") (pinfunction "C_C") (pintype "passive"))
      (node (ref "R1_BAT") (pin "1") (pinfunction "1_1") (pintype "passive"))
    )
    (net (code "23") (name "Net-(D2-CATHODE)") (class "Default")
      (node (ref "C1_BAT1") (pin "1") (pinfunction "1_1") (pintype "passive"))
      (node (ref "D2") (pin "1") (pinfunction "CATHODE_1") (pintype "bidirectional"))
      (node (ref "IC4") (pin "1") (pinfunction "VIN_1") (pintype "bidirectional"))
      (node (ref "IC4") (pin "3") (pinfunction "CE_3") (pintype "bidirectional"))
      (node (ref "Q1") (pin "2") (pinfunction "S_2") (pintype "bidirectional"))
    )
    (net (code "24") (name "Net-(D3-A)") (class "Default")
      (node (ref "C4") (pin "1") (pinfunction "1_1") (pintype "passive"))
      (node (ref "D3") (pin "2") (pinfunction "A_2") (pintype "bidirectional"))
      (node (ref "D4") (pin "1") (pinfunction "K_1") (pintype "bidirectional"))
    )
    (net (code "25") (name "Net-(D7-CATHODE)") (class "Default")
      (node (ref "D7") (pin "1") (pinfunction "CATHODE_1") (pintype "bidirectional"))
      (node (ref "R_CAPACITOR") (pin "2") (pinfunction "2_2") (pintype "passive"))
    )
    (net (code "26") (name "Net-(EPD_C1-Pad1)") (class "Default")
      (node (ref "EPD_C1") (pin "1") (pinfunction "1_1") (pintype "passive"))
      (node (ref "J1") (pin "4") (pinfunction "4_4") (pintype "bidirectional"))
    )
    (net (code "27") (name "Net-(EPD_C2-Pad1)") (class "Default")
      (node (ref "EPD_C2") (pin "1") (pinfunction "1_1") (pintype "passive"))
      (node (ref "J1") (pin "5") (pinfunction "5_5") (pintype "bidirectional"))
    )
    (net (code "28") (name "Net-(EPD_C6-Pad1)") (class "Default")
      (node (ref "EPD_C6") (pin "1") (pinfunction "1_1") (pintype "passive"))
      (node (ref "J1") (pin "18") (pinfunction "18_18") (pintype "bidirectional"))
    )
    (net (code "29") (name "Net-(EPD_C7-Pad1)") (class "Default")
      (node (ref "EPD_C7") (pin "1") (pinfunction "1_1") (pintype "passive"))
      (node (ref "J1") (pin "19") (pinfunction "19_19") (pintype "bidirectional"))
    )
    (net (code "30") (name "Net-(EPD_C8-Pad1)") (class "Default")
      (node (ref "EPD_C8") (pin "1") (pinfunction "1_1") (pintype "passive"))
      (node (ref "J1") (pin "20") (pinfunction "20_20") (pintype "bidirectional"))
    )
    (net (code "31") (name "Net-(EPD_C10-Pad1)") (class "Default")
      (node (ref "EPD_C10") (pin "1") (pinfunction "1_1") (pintype "passive"))
      (node (ref "J1") (pin "22") (pinfunction "22_22") (pintype "bidirectional"))
    )
    (net (code "32") (name "Net-(EPD_C12-Pad1)") (class "Default")
      (node (ref "EPD_C12") (pin "1") (pinfunction "1_1") (pintype "passive"))
      (node (ref "J1") (pin "24") (pinfunction "24_24") (pintype "bidirectional"))
    )
    (net (code "33") (name "Net-(IC1-CT)") (class "Default")
      (node (ref "C_DELAY") (pin "1") (pinfunction "1_1") (pintype "passive"))
      (node (ref "IC1") (pin "5") (pinfunction "CT_5") (pintype "bidirectional"))
    )
    (net (code "34") (name "Net-(J2-PadA5)") (class "Default")
      (node (ref "J2") (pin "A5") (pinfunction "A5_A5") (pintype "bidirectional"))
      (node (ref "R2-USB1") (pin "2") (pinfunction "2_2") (pintype "passive"))
    )
    (net (code "35") (name "Net-(J2-PadB5)") (class "Default")
      (node (ref "J2") (pin "B5") (pinfunction "B5_B5") (pintype "bidirectional"))
      (node (ref "R2-USB") (pin "1") (pinfunction "1_1") (pintype "passive"))
    )
    (net (code "36") (name "Net-(MCP73831-PROG)") (class "Default")
      (node (ref "MCP73831") (pin "5") (pinfunction "PROG_5") (pintype "input"))
      (node (ref "R2_BAT") (pin "2") (pinfunction "2_2") (pintype "passive"))
    )
    (net (code "37") (name "Net-(MCP73831-STAT)") (class "Default")
      (node (ref "MCP73831") (pin "1") (pinfunction "STAT_1") (pintype "output"))
      (node (ref "R1_BAT") (pin "2") (pinfunction "2_2") (pintype "passive"))
    )
    (net (code "38") (name "PREVGH") (class "Default")
      (node (ref "D5") (pin "1") (pinfunction "K_1") (pintype "bidirectional"))
      (node (ref "EPD_C9") (pin "1") (pinfunction "1_1") (pintype "passive"))
      (node (ref "J1") (pin "21") (pinfunction "21_21") (pintype "bidirectional"))
    )
    (net (code "39") (name "PREVGL") (class "Default")
      (node (ref "D4") (pin "2") (pinfunction "A_2") (pintype "bidirectional"))
      (node (ref "EPD_C11") (pin "1") (pinfunction "1_1") (pintype "passive"))
      (node (ref "J1") (pin "23") (pinfunction "23_23") (pintype "bidirectional"))
    )
    (net (code "40") (name "RESE") (class "Default")
      (node (ref "J1") (pin "3") (pinfunction "3_3") (pintype "bidirectional"))
      (node (ref "Q3") (pin "2") (pinfunction "S_2") (pintype "bidirectional"))
      (node (ref "R3") (pin "2") (pinfunction "2_2") (pintype "passive"))
    )
    (net (code "41") (name "RESE'") (class "Default")
      (node (ref "R2") (pin "2") (pinfunction "2_2") (pintype "passive"))
      (node (ref "R3") (pin "1") (pinfunction "1_1") (pintype "passive"))
      (node (ref "SJ1") (pin "2") (pinfunction "2_2") (pintype "passive"))
    )
    (net (code "42") (name "RESET") (class "Default")
      (node (ref "C5") (pin "1") (pinfunction "1_1") (pintype "passive"))
      (node (ref "IC1") (pin "1") (pinfunction "VOUT_1") (pintype "bidirectional"))
      (node (ref "RESET_BUTTON") (pin "3") (pinfunction "3_3") (pintype "passive"))
      (node (ref "RESET_BUTTON") (pin "4") (pinfunction "4_4") (pintype "passive"))
      (node (ref "R_RESET") (pin "1") (pinfunction "1_1") (pintype "passive"))
      (node (ref "U2") (pin "3") (pinfunction "EN_3") (pintype "input"))
    )
    (net (code "43") (name "RTC_RST") (class "Default")
      (node (ref "U2") (pin "16") (pinfunction "IO18_16") (pintype "bidirectional"))
      (node (ref "U3") (pin "4") (pinfunction "~{RST}_4") (pintype "input"))
    )
    (net (code "44") (name "RX") (class "Default")
      (node (ref "TP2") (pin "TP") (pinfunction "TP_TP") (pintype "input"))
      (node (ref "U2") (pin "24") (pinfunction "RXD0/GPIO17_24") (pintype "bidirectional"))
    )
    (net (code "45") (name "SCK") (class "Default")
      (node (ref "D10") (pin "2") (pinfunction "2_2") (pintype "passive"))
      (node (ref "J1") (pin "13") (pinfunction "13_13") (pintype "bidirectional"))
      (node (ref "J4") (pin "P5") (pinfunction "CLK_P5") (pintype "bidirectional"))
      (node (ref "R6") (pin "1") (pinfunction "1_1") (pintype "passive"))
      (node (ref "TP8") (pin "TP") (pinfunction "TP_TP") (pintype "input"))
      (node (ref "U1") (pin "6") (pinfunction "CLK_6") (pintype "input"))
      (node (ref "U2") (pin "6") (pinfunction "IO6_6") (pintype "bidirectional"))
    )
    (net (code "46") (name "SCL") (class "Default")
      (node (ref "J3") (pin "4") (pinfunction "4_4") (pintype "passive"))
      (node (ref "R2_PINH") (pin "1") (pinfunction "1_1") (pintype "passive"))
      (node (ref "SENSOR2") (pin "4") (pinfunction "SCK_4") (pintype "input"))
      (node (ref "U2") (pin "20") (pinfunction "IO22_20") (pintype "bidirectional"))
      (node (ref "U3") (pin "16") (pinfunction "SCL_16") (pintype "input"))
      (node (ref "U4") (pin "7") (pinfunction "SCL_7") (pintype "input"))
    )
    (net (code "47") (name "SDA") (class "Default")
      (node (ref "J3") (pin "3") (pinfunction "3_3") (pintype "passive"))
      (node (ref "R1_PINH") (pin "1") (pinfunction "1_1") (pintype "passive"))
      (node (ref "SENSOR2") (pin "3") (pinfunction "SDI_3") (pintype "bidirectional"))
      (node (ref "U2") (pin "19") (pinfunction "IO21_19") (pintype "bidirectional"))
      (node (ref "U3") (pin "15") (pinfunction "SDA_15") (pintype "bidirectional"))
      (node (ref "U4") (pin "8") (pinfunction "SDA_8") (pintype "bidirectional"))
    )
    (net (code "48") (name "SRC") (class "Default")
      (node (ref "C4") (pin "2") (pinfunction "2_2") (pintype "passive"))
      (node (ref "D5") (pin "2") (pinfunction "A_2") (pintype "bidirectional"))
      (node (ref "L1") (pin "1") (pinfunction "1_1") (pintype "passive"))
      (node (ref "Q3") (pin "3") (pinfunction "D_3") (pintype "bidirectional"))
    )
    (net (code "49") (name "SS_SD") (class "Default")
      (node (ref "D8") (pin "2") (pinfunction "2_2") (pintype "passive"))
      (node (ref "J4") (pin "P2") (pinfunction "CD/DAT3_P2") (pintype "bidirectional"))
      (node (ref "R10") (pin "1") (pinfunction "1_1") (pintype "passive"))
      (node (ref "U2") (pin "4") (pinfunction "IO4_4") (pintype "bidirectional"))
    )
    (net (code "50") (name "TX") (class "Default")
      (node (ref "TP1") (pin "TP") (pinfunction "TP_TP") (pintype "input"))
      (node (ref "U2") (pin "25") (pinfunction "TXD0/GPIO16_25") (pintype "bidirectional"))
    )
    (net (code "51") (name "USB_D+") (class "Default")
      (node (ref "D1") (pin "1") (pinfunction "I/O1_1_1") (pintype "bidirectional"))
      (node (ref "U2") (pin "14") (pinfunction "IO13_14") (pintype "bidirectional"))
    )
    (net (code "52") (name "USB_D-") (class "Default")
      (node (ref "D1") (pin "3") (pinfunction "I/O2_1_3") (pintype "bidirectional"))
      (node (ref "U2") (pin "13") (pinfunction "IO12_13") (pintype "bidirectional"))
    )
    (net (code "53") (name "VBAT") (class "Default")
      (node (ref "C2_BAT") (pin "1") (pinfunction "1_1") (pintype "passive"))
      (node (ref "MCP73831") (pin "3") (pinfunction "VBAT_3") (pintype "power_in"))
      (node (ref "Q1") (pin "3") (pinfunction "D_3") (pintype "bidirectional"))
      (node (ref "TP3") (pin "TP") (pinfunction "TP_TP") (pintype "input"))
      (node (ref "U4") (pin "2") (pinfunction "CELL_2") (pintype "power_in"))
      (node (ref "U4") (pin "3") (pinfunction "VDD_3") (pintype "power_in"))
    )
    (net (code "54") (name "VBUS") (class "Default")
      (node (ref "C1_BAT") (pin "1") (pinfunction "1_1") (pintype "passive"))
      (node (ref "C4_USB") (pin "1") (pinfunction "1_1") (pintype "passive"))
      (node (ref "C5_USB") (pin "1") (pinfunction "1_1") (pintype "passive"))
      (node (ref "CHG_LED") (pin "A") (pinfunction "A_A") (pintype "passive"))
      (node (ref "D1") (pin "5") (pinfunction "VBUS_5") (pintype "bidirectional"))
      (node (ref "D2") (pin "2") (pinfunction "ANODE_2") (pintype "bidirectional"))
      (node (ref "MCP73831") (pin "4") (pinfunction "VIN_4") (pintype "power_in"))
      (node (ref "PFMF.050.1") (pin "2") (pinfunction "2_2") (pintype "passive"))
      (node (ref "Q1") (pin "1") (pinfunction "G_1") (pintype "bidirectional"))
      (node (ref "R1_PWRUSB") (pin "2") (pinfunction "2_2") (pintype "passive"))
      (node (ref "TP14") (pin "TP") (pinfunction "TP_TP") (pintype "input"))
    )
    (net (code "55") (name "VRTC") (class "Default")
      (node (ref "C10_SUPERCAP") (pin "2") (pinfunction "2_2") (pintype "passive"))
      (node (ref "C8") (pin "1") (pinfunction "1_1") (pintype "passive"))
      (node (ref "R_CAPACITOR") (pin "1") (pinfunction "1_1") (pintype "passive"))
      (node (ref "U3") (pin "14") (pinfunction "VBAT_14") (pintype "power_in"))
    )
    (net (code "56") (name "VUSB") (class "Default")
      (node (ref "J2") (pin "A4") (pinfunction "A4_A4") (pintype "bidirectional"))
      (node (ref "J2") (pin "A9") (pinfunction "A9_A9") (pintype "bidirectional"))
      (node (ref "J2") (pin "B4") (pinfunction "B4_B4") (pintype "bidirectional"))
      (node (ref "J2") (pin "B9") (pinfunction "B9_B9") (pintype "bidirectional"))
      (node (ref "PFMF.050.1") (pin "1") (pinfunction "1_1") (pintype "passive"))
    )
    (net (code "57") (name "unconnected-(IC1-NC-Pad4)") (class "Default")
      (node (ref "IC1") (pin "4") (pinfunction "NC_4") (pintype "no_connect"))
    )
    (net (code "58") (name "unconnected-(IC4-NC-Pad4)") (class "Default")
      (node (ref "IC4") (pin "4") (pinfunction "NC_4") (pintype "no_connect"))
    )
    (net (code "59") (name "unconnected-(J1-Pad1)") (class "Default")
      (node (ref "J1") (pin "1") (pinfunction "1_1") (pintype "bidirectional"))
    )
    (net (code "60") (name "unconnected-(J1-Pad6)") (class "Default")
      (node (ref "J1") (pin "6") (pinfunction "6_6") (pintype "bidirectional"))
    )
    (net (code "61") (name "unconnected-(J1-Pad7)") (class "Default")
      (node (ref "J1") (pin "7") (pinfunction "7_7") (pintype "bidirectional"))
    )
    (net (code "62") (name "unconnected-(J2-PadA8)") (class "Default")
      (node (ref "J2") (pin "A8") (pinfunction "A8_A8") (pintype "bidirectional"))
    )
    (net (code "63") (name "unconnected-(J2-PadB8)") (class "Default")
      (node (ref "J2") (pin "B8") (pinfunction "B8_B8") (pintype "bidirectional"))
    )
    (net (code "64") (name "unconnected-(J4-DAT1-PadP8)") (class "Default")
      (node (ref "J4") (pin "P8") (pinfunction "DAT1_P8") (pintype "bidirectional"))
    )
    (net (code "65") (name "unconnected-(J4-DAT2-PadP1)") (class "Default")
      (node (ref "J4") (pin "P1") (pinfunction "DAT2_P1") (pintype "bidirectional"))
    )
    (net (code "66") (name "unconnected-(J4-DETECTION_1-PadS1)") (class "Default")
      (node (ref "J4") (pin "S1") (pinfunction "DETECTION_1_S1") (pintype "bidirectional"))
    )
    (net (code "67") (name "unconnected-(J4-DETECTION_2-PadS2)") (class "Default")
      (node (ref "J4") (pin "S2") (pinfunction "DETECTION_2_S2") (pintype "bidirectional"))
    )
    (net (code "68") (name "unconnected-(U2-NC-Pad22)") (class "Default")
      (node (ref "U2") (pin "22") (pinfunction "NC_22") (pintype "no_connect"))
    )
    (net (code "69") (name "unconnected-(U4-~{ALERT}-Pad5)") (class "Default")
      (node (ref "U4") (pin "5") (pinfunction "~{ALERT}_5") (pintype "output"))
    )
  )
)
